# LCD-OLINUXINO-4_3TS_Rev_A.net
KiCad netlist of a schematic drawn in EAGLE
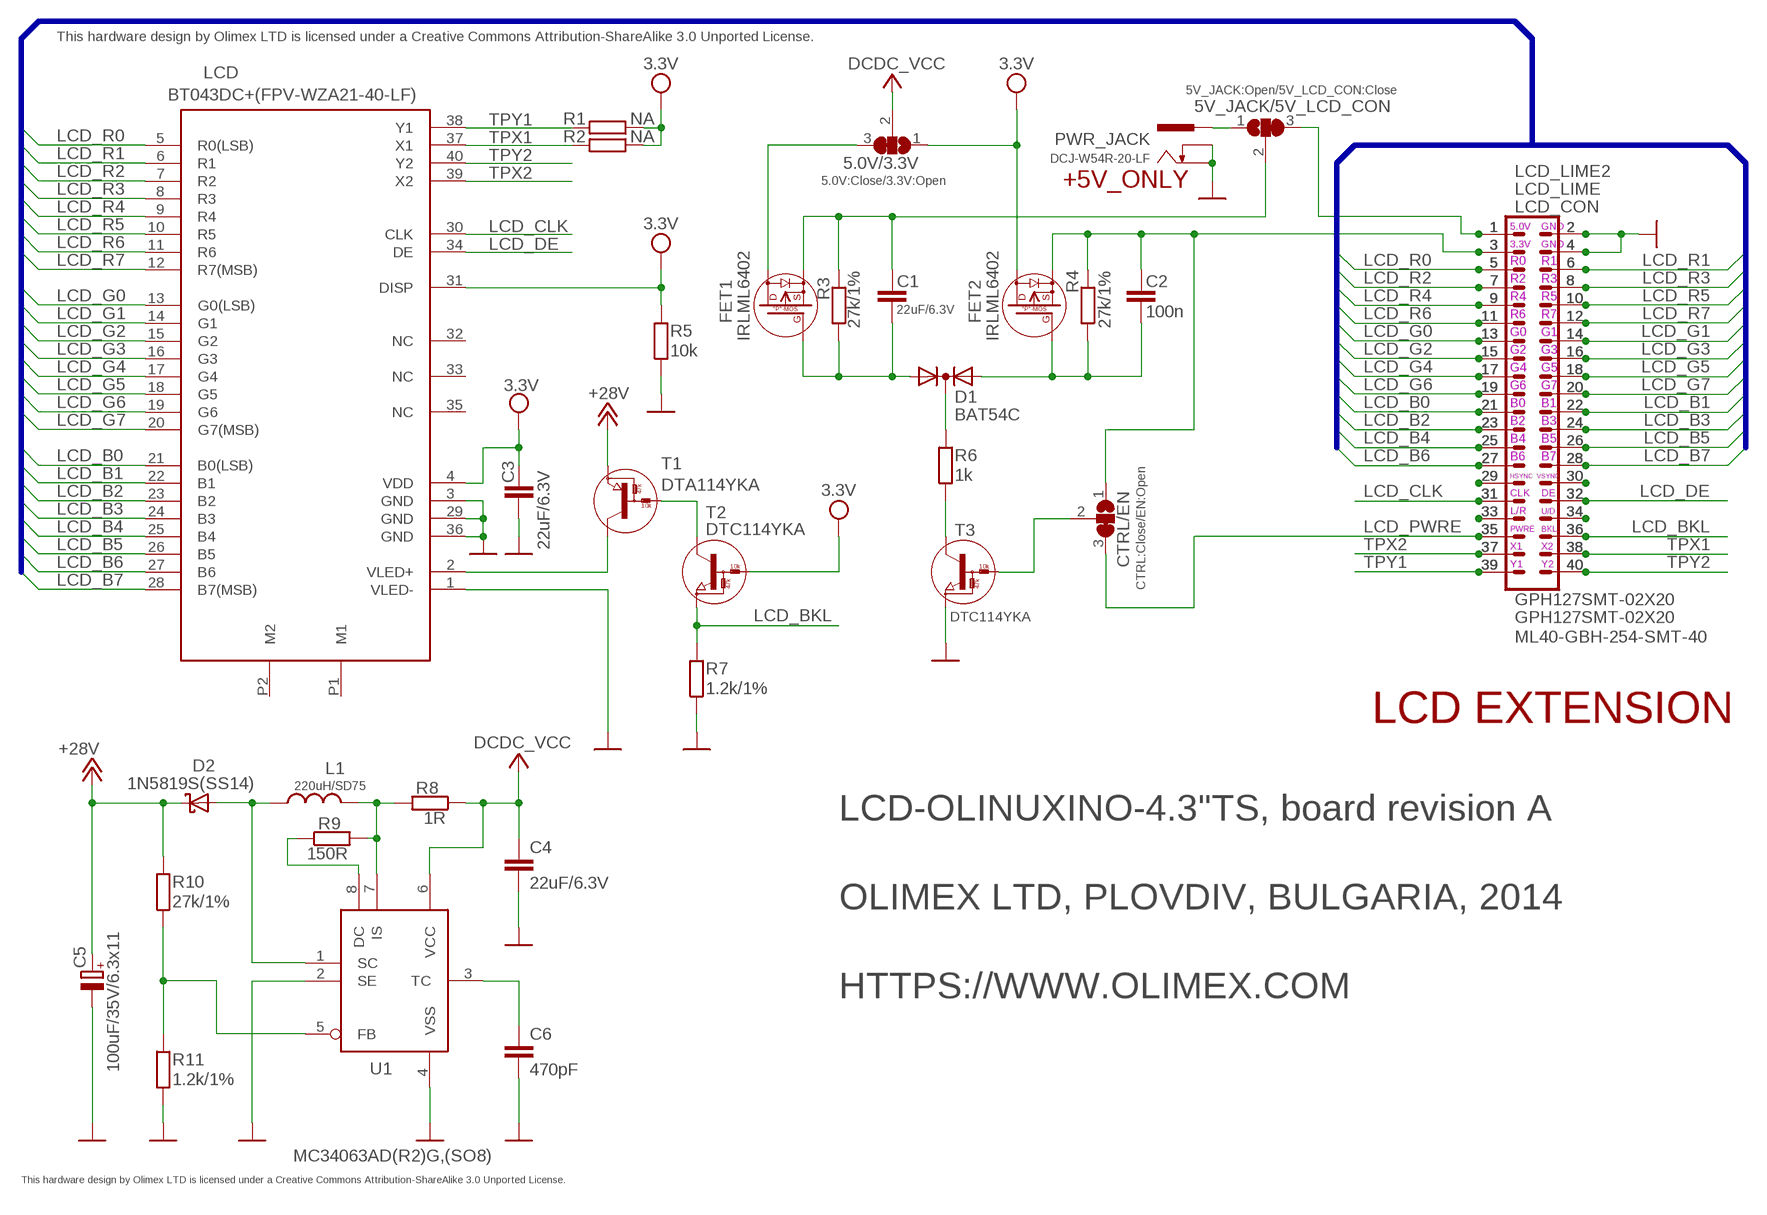
[diagram p0: schematic, sheet 1]

(export (version "E")
  (design (tool "Eeschema 10.0.6"))
  (components
    (comp (ref "5.0V/3.3V")
      (value "5.0V:Close/3.3V:Open")
      (footprint "eagle-import:SJ_2_SMALL_23_TIED")
      (libsource (lib "eagle-import") (part "SJ2W5"))
    )
    (comp (ref "5V_JACK/5V_LCD_CON")
      (value "5V_JACK:Open/5V_LCD_CON:Close")
      (footprint "eagle-import:SJ_2_SMALL")
      (libsource (lib "eagle-import") (part "SJ2W3"))
    )
    (comp (ref "C1")
      (value "22uF/6.3V")
      (footprint "eagle-import:C0603_DWS")
      (libsource (lib "eagle-import") (part "C-EUC0603_DWS"))
    )
    (comp (ref "C2")
      (value "100n")
      (footprint "eagle-import:C0603_DWS")
      (libsource (lib "eagle-import") (part "C-EUC0603_DWS"))
    )
    (comp (ref "C3")
      (value "22uF/6.3V")
      (footprint "eagle-import:C0603_DWS")
      (libsource (lib "eagle-import") (part "C-EUC0603_DWS"))
    )
    (comp (ref "C4")
      (value "22uF/6.3V")
      (footprint "eagle-import:C0603_DWS")
      (libsource (lib "eagle-import") (part "C-EUC0603_DWS"))
    )
    (comp (ref "C5")
      (value "100uF/35V/6.3x11")
      (footprint "eagle-import:CP6.3X11-H-M")
      (libsource (lib "eagle-import") (part "CPOL-EUH1M"))
    )
    (comp (ref "C6")
      (value "470pF")
      (footprint "eagle-import:C0603_DWS")
      (libsource (lib "eagle-import") (part "C-EUC0603_DWS"))
    )
    (comp (ref "CTRL/EN")
      (value "CTRL:Close/EN:Open")
      (footprint "eagle-import:SJ_2_SMALL_23_TIED")
      (libsource (lib "eagle-import") (part "SJ2W5"))
    )
    (comp (ref "D1")
      (value "BAT54C")
      (footprint "eagle-import:SOT23C")
      (libsource (lib "eagle-import") (part "DIODE_AC-CA_"))
    )
    (comp (ref "D2")
      (value "1N5819S(SS14)")
      (footprint "eagle-import:MLL-41")
      (libsource (lib "eagle-import") (part "SCHOTKKY7.62SS2"))
    )
    (comp (ref "FET1")
      (value "IRLML6402")
      (footprint "eagle-import:SOT23")
      (libsource (lib "eagle-import") (part "P-MOS+DIODIRLML6402"))
    )
    (comp (ref "FET2")
      (value "IRLML6402")
      (footprint "eagle-import:SOT23")
      (libsource (lib "eagle-import") (part "P-MOS+DIODIRLML6402"))
    )
    (comp (ref "L1")
      (value "220uH/SD75")
      (footprint "eagle-import:CLXXUH_SD73")
      (libsource (lib "eagle-import") (part "LCLXXUH_SD73"))
    )
    (comp (ref "LCD")
      (value "BT043DC+(FPV-WZA21-40-LF)")
      (footprint "eagle-import:FPV-WZA21-40-LF")
      (libsource (lib "eagle-import") (part "GFT043A13-LCD4.3{dblquote}"))
    )
    (comp (ref "LCD_CON")
      (value "ML40-GBH-254-SMT-40")
      (footprint "eagle-import:ML40-MALE(GBH-254-SMT-40)")
      (libsource (lib "eagle-import") (part "ML40-GBH-254-SMT-40"))
    )
    (comp (ref "LCD_LIME")
      (value "GPH127SMT-02X20")
      (footprint "eagle-import:YA-V36P-2X20-LF")
      (libsource (lib "eagle-import") (part "ML40YA-V36P-2X20-LF"))
    )
    (comp (ref "LCD_LIME2")
      (value "GPH127SMT-02X20")
      (footprint "eagle-import:GPH127SMT-02X20(PA-V16X-2X20-LF)")
      (libsource (lib "eagle-import") (part "ML40-GPH127SMT-02X20(PA-V16X-2X20-LF)"))
    )
    (comp (ref "PWR_JACK")
      (value "DCJ-W54R-20-LF")
      (footprint "eagle-import:PWR-JACK-SMD")
      (libsource (lib "eagle-import") (part "PWR-JAKDCJ-W"))
    )
    (comp (ref "R1")
      (value "NA")
      (footprint "eagle-import:R0603_5MIL_DWS")
      (libsource (lib "eagle-import") (part "R-EU_R0603_5MIL_DWS"))
    )
    (comp (ref "R2")
      (value "NA")
      (footprint "eagle-import:R0603_5MIL_DWS")
      (libsource (lib "eagle-import") (part "R-EU_R0603_5MIL_DWS"))
    )
    (comp (ref "R3")
      (value "27k/1%")
      (footprint "eagle-import:R0603_5MIL_DWS")
      (libsource (lib "eagle-import") (part "R-EU_R0603_5MIL_DWS"))
    )
    (comp (ref "R4")
      (value "27k/1%")
      (footprint "eagle-import:R0603_5MIL_DWS")
      (libsource (lib "eagle-import") (part "R-EU_R0603_5MIL_DWS"))
    )
    (comp (ref "R5")
      (value "10k")
      (footprint "eagle-import:R0603_5MIL_DWS")
      (libsource (lib "eagle-import") (part "R-EU_R0603_5MIL_DWS"))
    )
    (comp (ref "R6")
      (value "1k")
      (footprint "eagle-import:R0603_5MIL_DWS")
      (libsource (lib "eagle-import") (part "R-EU_R0603_5MIL_DWS"))
    )
    (comp (ref "R7")
      (value "1.2k/1%")
      (footprint "eagle-import:R0603_5MIL_DWS")
      (libsource (lib "eagle-import") (part "R-EU_R0603_5MIL_DWS"))
    )
    (comp (ref "R8")
      (value "1R")
      (footprint "eagle-import:R0805_5MIL_DWS")
      (libsource (lib "eagle-import") (part "R-EU_R0805_5MIL_DWS"))
    )
    (comp (ref "R9")
      (value "150R")
      (footprint "eagle-import:R0603_5MIL_DWS")
      (libsource (lib "eagle-import") (part "R-EU_R0603_5MIL_DWS"))
    )
    (comp (ref "R10")
      (value "27k/1%")
      (footprint "eagle-import:R0603_5MIL_DWS")
      (libsource (lib "eagle-import") (part "R-EU_R0603_5MIL_DWS"))
    )
    (comp (ref "R11")
      (value "1.2k/1%")
      (footprint "eagle-import:R0603_5MIL_DWS")
      (libsource (lib "eagle-import") (part "R-EU_R0603_5MIL_DWS"))
    )
    (comp (ref "T1")
      (value "DTA114YKA")
      (footprint "eagle-import:SOT-23")
      (libsource (lib "eagle-import") (part "DIGITAL_TRANSISTORS-PNPDTA114YKA"))
    )
    (comp (ref "T2")
      (value "DTC114YKA")
      (footprint "eagle-import:SOT-23")
      (libsource (lib "eagle-import") (part "DIGITAL_TRANSISTORS-NPNDTC114YKA"))
    )
    (comp (ref "T3")
      (value "DTC114YKA")
      (footprint "eagle-import:SOT-23")
      (libsource (lib "eagle-import") (part "DIGITAL_TRANSISTORS-NPNDTC114YKA"))
    )
    (comp (ref "U1")
      (value "MC34063AD(R2)G,(SO8)")
      (footprint "eagle-import:SO-8")
      (libsource (lib "eagle-import") (part "MC34063A2"))
    )
  )
  (nets
    (net (code "1") (name "+28V") (class "Default")
      (node (ref "C5") (pin "+") (pinfunction "+_+") (pintype "passive"))
      (node (ref "D2") (pin "K") (pinfunction "C_K") (pintype "passive"))
      (node (ref "R10") (pin "2") (pinfunction "2_2") (pintype "passive"))
      (node (ref "T1") (pin "2") (pinfunction "E_2") (pintype "passive"))
    )
    (net (code "2") (name "/LCD_B0") (class "Default")
      (node (ref "LCD") (pin "21") (pinfunction "B0(LSB)_21") (pintype "input"))
      (node (ref "LCD_CON") (pin "21") (pinfunction "21_21") (pintype "passive"))
      (node (ref "LCD_LIME") (pin "21") (pinfunction "21_21") (pintype "passive"))
      (node (ref "LCD_LIME2") (pin "21") (pinfunction "21_21") (pintype "passive"))
    )
    (net (code "3") (name "/LCD_B1") (class "Default")
      (node (ref "LCD") (pin "22") (pinfunction "B1_22") (pintype "input"))
      (node (ref "LCD_CON") (pin "22") (pinfunction "22_22") (pintype "passive"))
      (node (ref "LCD_LIME") (pin "22") (pinfunction "22_22") (pintype "passive"))
      (node (ref "LCD_LIME2") (pin "22") (pinfunction "22_22") (pintype "passive"))
    )
    (net (code "4") (name "/LCD_B2") (class "Default")
      (node (ref "LCD") (pin "23") (pinfunction "B2_23") (pintype "input"))
      (node (ref "LCD_CON") (pin "23") (pinfunction "23_23") (pintype "passive"))
      (node (ref "LCD_LIME") (pin "23") (pinfunction "23_23") (pintype "passive"))
      (node (ref "LCD_LIME2") (pin "23") (pinfunction "23_23") (pintype "passive"))
    )
    (net (code "5") (name "/LCD_B3") (class "Default")
      (node (ref "LCD") (pin "24") (pinfunction "B3_24") (pintype "input"))
      (node (ref "LCD_CON") (pin "24") (pinfunction "24_24") (pintype "passive"))
      (node (ref "LCD_LIME") (pin "24") (pinfunction "24_24") (pintype "passive"))
      (node (ref "LCD_LIME2") (pin "24") (pinfunction "24_24") (pintype "passive"))
    )
    (net (code "6") (name "/LCD_B4") (class "Default")
      (node (ref "LCD") (pin "25") (pinfunction "B4_25") (pintype "input"))
      (node (ref "LCD_CON") (pin "25") (pinfunction "25_25") (pintype "passive"))
      (node (ref "LCD_LIME") (pin "25") (pinfunction "25_25") (pintype "passive"))
      (node (ref "LCD_LIME2") (pin "25") (pinfunction "25_25") (pintype "passive"))
    )
    (net (code "7") (name "/LCD_B5") (class "Default")
      (node (ref "LCD") (pin "26") (pinfunction "B5_26") (pintype "input"))
      (node (ref "LCD_CON") (pin "26") (pinfunction "26_26") (pintype "passive"))
      (node (ref "LCD_LIME") (pin "26") (pinfunction "26_26") (pintype "passive"))
      (node (ref "LCD_LIME2") (pin "26") (pinfunction "26_26") (pintype "passive"))
    )
    (net (code "8") (name "/LCD_B6") (class "Default")
      (node (ref "LCD") (pin "27") (pinfunction "B6_27") (pintype "input"))
      (node (ref "LCD_CON") (pin "27") (pinfunction "27_27") (pintype "passive"))
      (node (ref "LCD_LIME") (pin "27") (pinfunction "27_27") (pintype "passive"))
      (node (ref "LCD_LIME2") (pin "27") (pinfunction "27_27") (pintype "passive"))
    )
    (net (code "9") (name "/LCD_B7") (class "Default")
      (node (ref "LCD") (pin "28") (pinfunction "B7(MSB)_28") (pintype "input"))
      (node (ref "LCD_CON") (pin "28") (pinfunction "28_28") (pintype "passive"))
      (node (ref "LCD_LIME") (pin "28") (pinfunction "28_28") (pintype "passive"))
      (node (ref "LCD_LIME2") (pin "28") (pinfunction "28_28") (pintype "passive"))
    )
    (net (code "10") (name "/LCD_BKL") (class "Default")
      (node (ref "LCD_CON") (pin "36") (pinfunction "36_36") (pintype "passive"))
      (node (ref "LCD_LIME") (pin "36") (pinfunction "36_36") (pintype "passive"))
      (node (ref "LCD_LIME2") (pin "36") (pinfunction "36_36") (pintype "passive"))
      (node (ref "R7") (pin "2") (pinfunction "2_2") (pintype "passive"))
      (node (ref "T2") (pin "2") (pinfunction "E_2") (pintype "passive"))
    )
    (net (code "11") (name "/LCD_CLK") (class "Default")
      (node (ref "LCD") (pin "30") (pinfunction "CLK_30") (pintype "input"))
      (node (ref "LCD_CON") (pin "31") (pinfunction "31_31") (pintype "passive"))
      (node (ref "LCD_LIME") (pin "31") (pinfunction "31_31") (pintype "passive"))
      (node (ref "LCD_LIME2") (pin "31") (pinfunction "31_31") (pintype "passive"))
    )
    (net (code "12") (name "/LCD_DE") (class "Default")
      (node (ref "LCD") (pin "34") (pinfunction "DE_34") (pintype "input"))
      (node (ref "LCD_CON") (pin "32") (pinfunction "32_32") (pintype "passive"))
      (node (ref "LCD_LIME") (pin "32") (pinfunction "32_32") (pintype "passive"))
      (node (ref "LCD_LIME2") (pin "32") (pinfunction "32_32") (pintype "passive"))
    )
    (net (code "13") (name "/LCD_G0") (class "Default")
      (node (ref "LCD") (pin "13") (pinfunction "G0(LSB)_13") (pintype "input"))
      (node (ref "LCD_CON") (pin "13") (pinfunction "13_13") (pintype "passive"))
      (node (ref "LCD_LIME") (pin "13") (pinfunction "13_13") (pintype "passive"))
      (node (ref "LCD_LIME2") (pin "13") (pinfunction "13_13") (pintype "passive"))
    )
    (net (code "14") (name "/LCD_G1") (class "Default")
      (node (ref "LCD") (pin "14") (pinfunction "G1_14") (pintype "input"))
      (node (ref "LCD_CON") (pin "14") (pinfunction "14_14") (pintype "passive"))
      (node (ref "LCD_LIME") (pin "14") (pinfunction "14_14") (pintype "passive"))
      (node (ref "LCD_LIME2") (pin "14") (pinfunction "14_14") (pintype "passive"))
    )
    (net (code "15") (name "/LCD_G2") (class "Default")
      (node (ref "LCD") (pin "15") (pinfunction "G2_15") (pintype "input"))
      (node (ref "LCD_CON") (pin "15") (pinfunction "15_15") (pintype "passive"))
      (node (ref "LCD_LIME") (pin "15") (pinfunction "15_15") (pintype "passive"))
      (node (ref "LCD_LIME2") (pin "15") (pinfunction "15_15") (pintype "passive"))
    )
    (net (code "16") (name "/LCD_G3") (class "Default")
      (node (ref "LCD") (pin "16") (pinfunction "G3_16") (pintype "input"))
      (node (ref "LCD_CON") (pin "16") (pinfunction "16_16") (pintype "passive"))
      (node (ref "LCD_LIME") (pin "16") (pinfunction "16_16") (pintype "passive"))
      (node (ref "LCD_LIME2") (pin "16") (pinfunction "16_16") (pintype "passive"))
    )
    (net (code "17") (name "/LCD_G4") (class "Default")
      (node (ref "LCD") (pin "17") (pinfunction "G4_17") (pintype "input"))
      (node (ref "LCD_CON") (pin "17") (pinfunction "17_17") (pintype "passive"))
      (node (ref "LCD_LIME") (pin "17") (pinfunction "17_17") (pintype "passive"))
      (node (ref "LCD_LIME2") (pin "17") (pinfunction "17_17") (pintype "passive"))
    )
    (net (code "18") (name "/LCD_G5") (class "Default")
      (node (ref "LCD") (pin "18") (pinfunction "G5_18") (pintype "input"))
      (node (ref "LCD_CON") (pin "18") (pinfunction "18_18") (pintype "passive"))
      (node (ref "LCD_LIME") (pin "18") (pinfunction "18_18") (pintype "passive"))
      (node (ref "LCD_LIME2") (pin "18") (pinfunction "18_18") (pintype "passive"))
    )
    (net (code "19") (name "/LCD_G6") (class "Default")
      (node (ref "LCD") (pin "19") (pinfunction "G6_19") (pintype "input"))
      (node (ref "LCD_CON") (pin "19") (pinfunction "19_19") (pintype "passive"))
      (node (ref "LCD_LIME") (pin "19") (pinfunction "19_19") (pintype "passive"))
      (node (ref "LCD_LIME2") (pin "19") (pinfunction "19_19") (pintype "passive"))
    )
    (net (code "20") (name "/LCD_G7") (class "Default")
      (node (ref "LCD") (pin "20") (pinfunction "G7(MSB)_20") (pintype "input"))
      (node (ref "LCD_CON") (pin "20") (pinfunction "20_20") (pintype "passive"))
      (node (ref "LCD_LIME") (pin "20") (pinfunction "20_20") (pintype "passive"))
      (node (ref "LCD_LIME2") (pin "20") (pinfunction "20_20") (pintype "passive"))
    )
    (net (code "21") (name "/LCD_PWRE") (class "Default")
      (node (ref "CTRL/EN") (pin "3") (pinfunction "3_3") (pintype "passive"))
      (node (ref "LCD_CON") (pin "35") (pinfunction "35_35") (pintype "passive"))
      (node (ref "LCD_LIME") (pin "35") (pinfunction "35_35") (pintype "passive"))
      (node (ref "LCD_LIME2") (pin "35") (pinfunction "35_35") (pintype "passive"))
    )
    (net (code "22") (name "/LCD_R0") (class "Default")
      (node (ref "LCD") (pin "5") (pinfunction "R0(LSB)_5") (pintype "input"))
      (node (ref "LCD_CON") (pin "5") (pinfunction "5_5") (pintype "passive"))
      (node (ref "LCD_LIME") (pin "5") (pinfunction "5_5") (pintype "passive"))
      (node (ref "LCD_LIME2") (pin "5") (pinfunction "5_5") (pintype "passive"))
    )
    (net (code "23") (name "/LCD_R1") (class "Default")
      (node (ref "LCD") (pin "6") (pinfunction "R1_6") (pintype "input"))
      (node (ref "LCD_CON") (pin "6") (pinfunction "6_6") (pintype "passive"))
      (node (ref "LCD_LIME") (pin "6") (pinfunction "6_6") (pintype "passive"))
      (node (ref "LCD_LIME2") (pin "6") (pinfunction "6_6") (pintype "passive"))
    )
    (net (code "24") (name "/LCD_R2") (class "Default")
      (node (ref "LCD") (pin "7") (pinfunction "R2_7") (pintype "input"))
      (node (ref "LCD_CON") (pin "7") (pinfunction "7_7") (pintype "passive"))
      (node (ref "LCD_LIME") (pin "7") (pinfunction "7_7") (pintype "passive"))
      (node (ref "LCD_LIME2") (pin "7") (pinfunction "7_7") (pintype "passive"))
    )
    (net (code "25") (name "/LCD_R3") (class "Default")
      (node (ref "LCD") (pin "8") (pinfunction "R3_8") (pintype "input"))
      (node (ref "LCD_CON") (pin "8") (pinfunction "8_8") (pintype "passive"))
      (node (ref "LCD_LIME") (pin "8") (pinfunction "8_8") (pintype "passive"))
      (node (ref "LCD_LIME2") (pin "8") (pinfunction "8_8") (pintype "passive"))
    )
    (net (code "26") (name "/LCD_R4") (class "Default")
      (node (ref "LCD") (pin "9") (pinfunction "R4_9") (pintype "input"))
      (node (ref "LCD_CON") (pin "9") (pinfunction "9_9") (pintype "passive"))
      (node (ref "LCD_LIME") (pin "9") (pinfunction "9_9") (pintype "passive"))
      (node (ref "LCD_LIME2") (pin "9") (pinfunction "9_9") (pintype "passive"))
    )
    (net (code "27") (name "/LCD_R5") (class "Default")
      (node (ref "LCD") (pin "10") (pinfunction "R5_10") (pintype "input"))
      (node (ref "LCD_CON") (pin "10") (pinfunction "10_10") (pintype "passive"))
      (node (ref "LCD_LIME") (pin "10") (pinfunction "10_10") (pintype "passive"))
      (node (ref "LCD_LIME2") (pin "10") (pinfunction "10_10") (pintype "passive"))
    )
    (net (code "28") (name "/LCD_R6") (class "Default")
      (node (ref "LCD") (pin "11") (pinfunction "R6_11") (pintype "input"))
      (node (ref "LCD_CON") (pin "11") (pinfunction "11_11") (pintype "passive"))
      (node (ref "LCD_LIME") (pin "11") (pinfunction "11_11") (pintype "passive"))
      (node (ref "LCD_LIME2") (pin "11") (pinfunction "11_11") (pintype "passive"))
    )
    (net (code "29") (name "/LCD_R7") (class "Default")
      (node (ref "LCD") (pin "12") (pinfunction "R7(MSB)_12") (pintype "input"))
      (node (ref "LCD_CON") (pin "12") (pinfunction "12_12") (pintype "passive"))
      (node (ref "LCD_LIME") (pin "12") (pinfunction "12_12") (pintype "passive"))
      (node (ref "LCD_LIME2") (pin "12") (pinfunction "12_12") (pintype "passive"))
    )
    (net (code "30") (name "/TPX1") (class "Default")
      (node (ref "LCD") (pin "37") (pinfunction "X1_37") (pintype "bidirectional"))
      (node (ref "LCD_CON") (pin "38") (pinfunction "38_38") (pintype "passive"))
      (node (ref "LCD_LIME") (pin "38") (pinfunction "38_38") (pintype "passive"))
      (node (ref "LCD_LIME2") (pin "38") (pinfunction "38_38") (pintype "passive"))
      (node (ref "R2") (pin "2") (pinfunction "2_2") (pintype "passive"))
    )
    (net (code "31") (name "/TPX2") (class "Default")
      (node (ref "LCD") (pin "39") (pinfunction "X2_39") (pintype "bidirectional"))
      (node (ref "LCD_CON") (pin "37") (pinfunction "37_37") (pintype "passive"))
      (node (ref "LCD_LIME") (pin "37") (pinfunction "37_37") (pintype "passive"))
      (node (ref "LCD_LIME2") (pin "37") (pinfunction "37_37") (pintype "passive"))
    )
    (net (code "32") (name "/TPY1") (class "Default")
      (node (ref "LCD") (pin "38") (pinfunction "Y1_38") (pintype "bidirectional"))
      (node (ref "LCD_CON") (pin "39") (pinfunction "39_39") (pintype "passive"))
      (node (ref "LCD_LIME") (pin "39") (pinfunction "39_39") (pintype "passive"))
      (node (ref "LCD_LIME2") (pin "39") (pinfunction "39_39") (pintype "passive"))
      (node (ref "R1") (pin "2") (pinfunction "2_2") (pintype "passive"))
    )
    (net (code "33") (name "/TPY2") (class "Default")
      (node (ref "LCD") (pin "40") (pinfunction "Y2_40") (pintype "bidirectional"))
      (node (ref "LCD_CON") (pin "40") (pinfunction "40_40") (pintype "passive"))
      (node (ref "LCD_LIME") (pin "40") (pinfunction "40_40") (pintype "passive"))
      (node (ref "LCD_LIME2") (pin "40") (pinfunction "40_40") (pintype "passive"))
    )
    (net (code "34") (name "3.3V") (class "Default")
      (node (ref "5.0V/3.3V") (pin "1") (pinfunction "1_1") (pintype "passive"))
      (node (ref "C3") (pin "1") (pinfunction "1_1") (pintype "passive"))
      (node (ref "FET2") (pin "3") (pinfunction "D_3") (pintype "passive"))
      (node (ref "LCD") (pin "31") (pinfunction "DISP_31") (pintype "input"))
      (node (ref "LCD") (pin "4") (pinfunction "VDD_4") (pintype "power_in"))
      (node (ref "R1") (pin "1") (pinfunction "1_1") (pintype "passive"))
      (node (ref "R2") (pin "1") (pinfunction "1_1") (pintype "passive"))
      (node (ref "R5") (pin "2") (pinfunction "2_2") (pintype "passive"))
      (node (ref "T2") (pin "1") (pinfunction "B_1") (pintype "passive"))
    )
    (net (code "35") (name "DCDC_VCC") (class "Default")
      (node (ref "5.0V/3.3V") (pin "2") (pinfunction "2_2") (pintype "passive"))
      (node (ref "C4") (pin "1") (pinfunction "1_1") (pintype "passive"))
      (node (ref "R8") (pin "1") (pinfunction "1_1") (pintype "passive"))
      (node (ref "U1") (pin "6") (pinfunction "VCC_6") (pintype "power_in"))
    )
    (net (code "36") (name "GND") (class "Default")
      (node (ref "C3") (pin "2") (pinfunction "2_2") (pintype "passive"))
      (node (ref "C4") (pin "2") (pinfunction "2_2") (pintype "passive"))
      (node (ref "C5") (pin "-") (pinfunction "-_-") (pintype "passive"))
      (node (ref "C6") (pin "2") (pinfunction "2_2") (pintype "passive"))
      (node (ref "LCD") (pin "1") (pinfunction "VLED-_1") (pintype "power_in"))
      (node (ref "LCD") (pin "29") (pinfunction "GND_29") (pintype "power_in"))
      (node (ref "LCD") (pin "3") (pinfunction "GND_3") (pintype "power_in"))
      (node (ref "LCD") (pin "36") (pinfunction "GND_36") (pintype "power_in"))
      (node (ref "LCD_CON") (pin "2") (pinfunction "2_2") (pintype "passive"))
      (node (ref "LCD_CON") (pin "4") (pinfunction "4_4") (pintype "passive"))
      (node (ref "LCD_LIME") (pin "2") (pinfunction "2_2") (pintype "passive"))
      (node (ref "LCD_LIME") (pin "4") (pinfunction "4_4") (pintype "passive"))
      (node (ref "LCD_LIME2") (pin "2") (pinfunction "2_2") (pintype "passive"))
      (node (ref "LCD_LIME2") (pin "4") (pinfunction "4_4") (pintype "passive"))
      (node (ref "PWR_JACK") (pin "2") (pinfunction "-_2") (pintype "passive"))
      (node (ref "PWR_JACK") (pin "3") (pinfunction "--_3") (pintype "passive"))
      (node (ref "R11") (pin "1") (pinfunction "1_1") (pintype "passive"))
      (node (ref "R5") (pin "1") (pinfunction "1_1") (pintype "passive"))
      (node (ref "R7") (pin "1") (pinfunction "1_1") (pintype "passive"))
      (node (ref "T3") (pin "2") (pinfunction "E_2") (pintype "passive"))
      (node (ref "U1") (pin "2") (pinfunction "SE_2") (pintype "bidirectional"))
      (node (ref "U1") (pin "4") (pinfunction "VSS_4") (pintype "power_in"))
    )
    (net (code "37") (name "Net-(5V_JACK/5V_LCD_CON-Pad3)") (class "Default")
      (node (ref "5V_JACK/5V_LCD_CON") (pin "3") (pinfunction "3_3") (pintype "passive"))
      (node (ref "LCD_CON") (pin "1") (pinfunction "1_1") (pintype "passive"))
      (node (ref "LCD_LIME") (pin "1") (pinfunction "1_1") (pintype "passive"))
      (node (ref "LCD_LIME2") (pin "1") (pinfunction "1_1") (pintype "passive"))
    )
    (net (code "38") (name "Net-(D1-A1)") (class "Default")
      (node (ref "C2") (pin "2") (pinfunction "2_2") (pintype "passive"))
      (node (ref "D1") (pin "1") (pinfunction "A1_1") (pintype "passive"))
      (node (ref "FET2") (pin "1") (pinfunction "G_1") (pintype "passive"))
      (node (ref "R4") (pin "1") (pinfunction "1_1") (pintype "passive"))
    )
    (net (code "39") (name "Net-(D1-A2)") (class "Default")
      (node (ref "C1") (pin "2") (pinfunction "2_2") (pintype "passive"))
      (node (ref "D1") (pin "2") (pinfunction "A2_2") (pintype "passive"))
      (node (ref "FET1") (pin "1") (pinfunction "G_1") (pintype "passive"))
      (node (ref "R3") (pin "1") (pinfunction "1_1") (pintype "passive"))
    )
    (net (code "40") (name "Net-(D1-K)") (class "Default")
      (node (ref "D1") (pin "3") (pinfunction "K_3") (pintype "passive"))
      (node (ref "R6") (pin "2") (pinfunction "2_2") (pintype "passive"))
    )
    (net (code "41") (name "Net-(FET1-D)") (class "Default")
      (node (ref "5.0V/3.3V") (pin "3") (pinfunction "3_3") (pintype "passive"))
      (node (ref "FET1") (pin "3") (pinfunction "D_3") (pintype "passive"))
    )
    (net (code "42") (name "Net-(FET1-S)") (class "Default")
      (node (ref "5V_JACK/5V_LCD_CON") (pin "2") (pinfunction "2_2") (pintype "passive"))
      (node (ref "C1") (pin "1") (pinfunction "1_1") (pintype "passive"))
      (node (ref "FET1") (pin "2") (pinfunction "S_2") (pintype "passive"))
      (node (ref "R3") (pin "2") (pinfunction "2_2") (pintype "passive"))
    )
    (net (code "43") (name "Net-(FET2-S)") (class "Default")
      (node (ref "C2") (pin "1") (pinfunction "1_1") (pintype "passive"))
      (node (ref "CTRL/EN") (pin "1") (pinfunction "1_1") (pintype "passive"))
      (node (ref "FET2") (pin "2") (pinfunction "S_2") (pintype "passive"))
      (node (ref "LCD_CON") (pin "3") (pinfunction "3_3") (pintype "passive"))
      (node (ref "LCD_LIME") (pin "3") (pinfunction "3_3") (pintype "passive"))
      (node (ref "LCD_LIME2") (pin "3") (pinfunction "3_3") (pintype "passive"))
      (node (ref "R4") (pin "2") (pinfunction "2_2") (pintype "passive"))
    )
    (net (code "44") (name "Net-(LCD-VLED+)") (class "Default")
      (node (ref "LCD") (pin "2") (pinfunction "VLED+_2") (pintype "power_in"))
      (node (ref "T1") (pin "3") (pinfunction "C_3") (pintype "passive"))
    )
    (net (code "45") (name "Net-(LCD_CON-Pad29)") (class "Default")
      (node (ref "LCD_CON") (pin "29") (pinfunction "29_29") (pintype "passive"))
      (node (ref "LCD_LIME") (pin "29") (pinfunction "29_29") (pintype "passive"))
      (node (ref "LCD_LIME2") (pin "29") (pinfunction "29_29") (pintype "passive"))
    )
    (net (code "46") (name "Net-(LCD_CON-Pad30)") (class "Default")
      (node (ref "LCD_CON") (pin "30") (pinfunction "30_30") (pintype "passive"))
      (node (ref "LCD_LIME") (pin "30") (pinfunction "30_30") (pintype "passive"))
      (node (ref "LCD_LIME2") (pin "30") (pinfunction "30_30") (pintype "passive"))
    )
    (net (code "47") (name "Net-(LCD_CON-Pad33)") (class "Default")
      (node (ref "LCD_CON") (pin "33") (pinfunction "33_33") (pintype "passive"))
      (node (ref "LCD_LIME") (pin "33") (pinfunction "33_33") (pintype "passive"))
      (node (ref "LCD_LIME2") (pin "33") (pinfunction "33_33") (pintype "passive"))
    )
    (net (code "48") (name "Net-(LCD_CON-Pad34)") (class "Default")
      (node (ref "LCD_CON") (pin "34") (pinfunction "34_34") (pintype "passive"))
      (node (ref "LCD_LIME") (pin "34") (pinfunction "34_34") (pintype "passive"))
      (node (ref "LCD_LIME2") (pin "34") (pinfunction "34_34") (pintype "passive"))
    )
    (net (code "49") (name "Net-(PWR_JACK-+)") (class "Default")
      (node (ref "5V_JACK/5V_LCD_CON") (pin "1") (pinfunction "1_1") (pintype "passive"))
      (node (ref "PWR_JACK") (pin "1") (pinfunction "+_1") (pintype "passive"))
    )
    (net (code "50") (name "Net-(T1-B)") (class "Default")
      (node (ref "T1") (pin "1") (pinfunction "B_1") (pintype "passive"))
      (node (ref "T2") (pin "3") (pinfunction "C_3") (pintype "passive"))
    )
    (net (code "51") (name "Net-(T3-B)") (class "Default")
      (node (ref "CTRL/EN") (pin "2") (pinfunction "2_2") (pintype "passive"))
      (node (ref "T3") (pin "1") (pinfunction "B_1") (pintype "passive"))
    )
    (net (code "52") (name "Net-(T3-C)") (class "Default")
      (node (ref "R6") (pin "1") (pinfunction "1_1") (pintype "passive"))
      (node (ref "T3") (pin "3") (pinfunction "C_3") (pintype "passive"))
    )
    (net (code "53") (name "Net-(U1-DC)") (class "Default")
      (node (ref "R9") (pin "1") (pinfunction "1_1") (pintype "passive"))
      (node (ref "U1") (pin "8") (pinfunction "DC_8") (pintype "open_collector"))
    )
    (net (code "54") (name "Net-(U1-FB)") (class "Default")
      (node (ref "R10") (pin "1") (pinfunction "1_1") (pintype "passive"))
      (node (ref "R11") (pin "2") (pinfunction "2_2") (pintype "passive"))
      (node (ref "U1") (pin "5") (pinfunction "FB_5") (pintype "input"))
    )
    (net (code "55") (name "Net-(U1-IS)") (class "Default")
      (node (ref "L1") (pin "1") (pinfunction "1_1") (pintype "passive"))
      (node (ref "R8") (pin "2") (pinfunction "2_2") (pintype "passive"))
      (node (ref "R9") (pin "2") (pinfunction "2_2") (pintype "passive"))
      (node (ref "U1") (pin "7") (pinfunction "IS_7") (pintype "bidirectional"))
    )
    (net (code "56") (name "Net-(U1-SC)") (class "Default")
      (node (ref "D2") (pin "A") (pinfunction "A_A") (pintype "passive"))
      (node (ref "L1") (pin "2") (pinfunction "2_2") (pintype "passive"))
      (node (ref "U1") (pin "1") (pinfunction "SC_1") (pintype "open_collector"))
    )
    (net (code "57") (name "Net-(U1-TC)") (class "Default")
      (node (ref "C6") (pin "1") (pinfunction "1_1") (pintype "passive"))
      (node (ref "U1") (pin "3") (pinfunction "TC_3") (pintype "bidirectional"))
    )
    (net (code "58") (name "unconnected-(LCD-M1-PadP1)") (class "Default")
      (node (ref "LCD") (pin "P1") (pinfunction "M1_P1") (pintype "passive"))
    )
    (net (code "59") (name "unconnected-(LCD-M2-PadP2)") (class "Default")
      (node (ref "LCD") (pin "P2") (pinfunction "M2_P2") (pintype "passive"))
    )
    (net (code "60") (name "unconnected-(LCD-NC-Pad32)") (class "Default")
      (node (ref "LCD") (pin "32") (pinfunction "NC_32") (pintype "no_connect"))
    )
    (net (code "61") (name "unconnected-(LCD-NC-Pad33)") (class "Default")
      (node (ref "LCD") (pin "33") (pinfunction "NC_33") (pintype "no_connect"))
    )
    (net (code "62") (name "unconnected-(LCD-NC-Pad35)") (class "Default")
      (node (ref "LCD") (pin "35") (pinfunction "NC_35") (pintype "no_connect"))
    )
  )
)
